# MegaShieldTrioV2.net
KiCad netlist of a schematic drawn in EAGLE
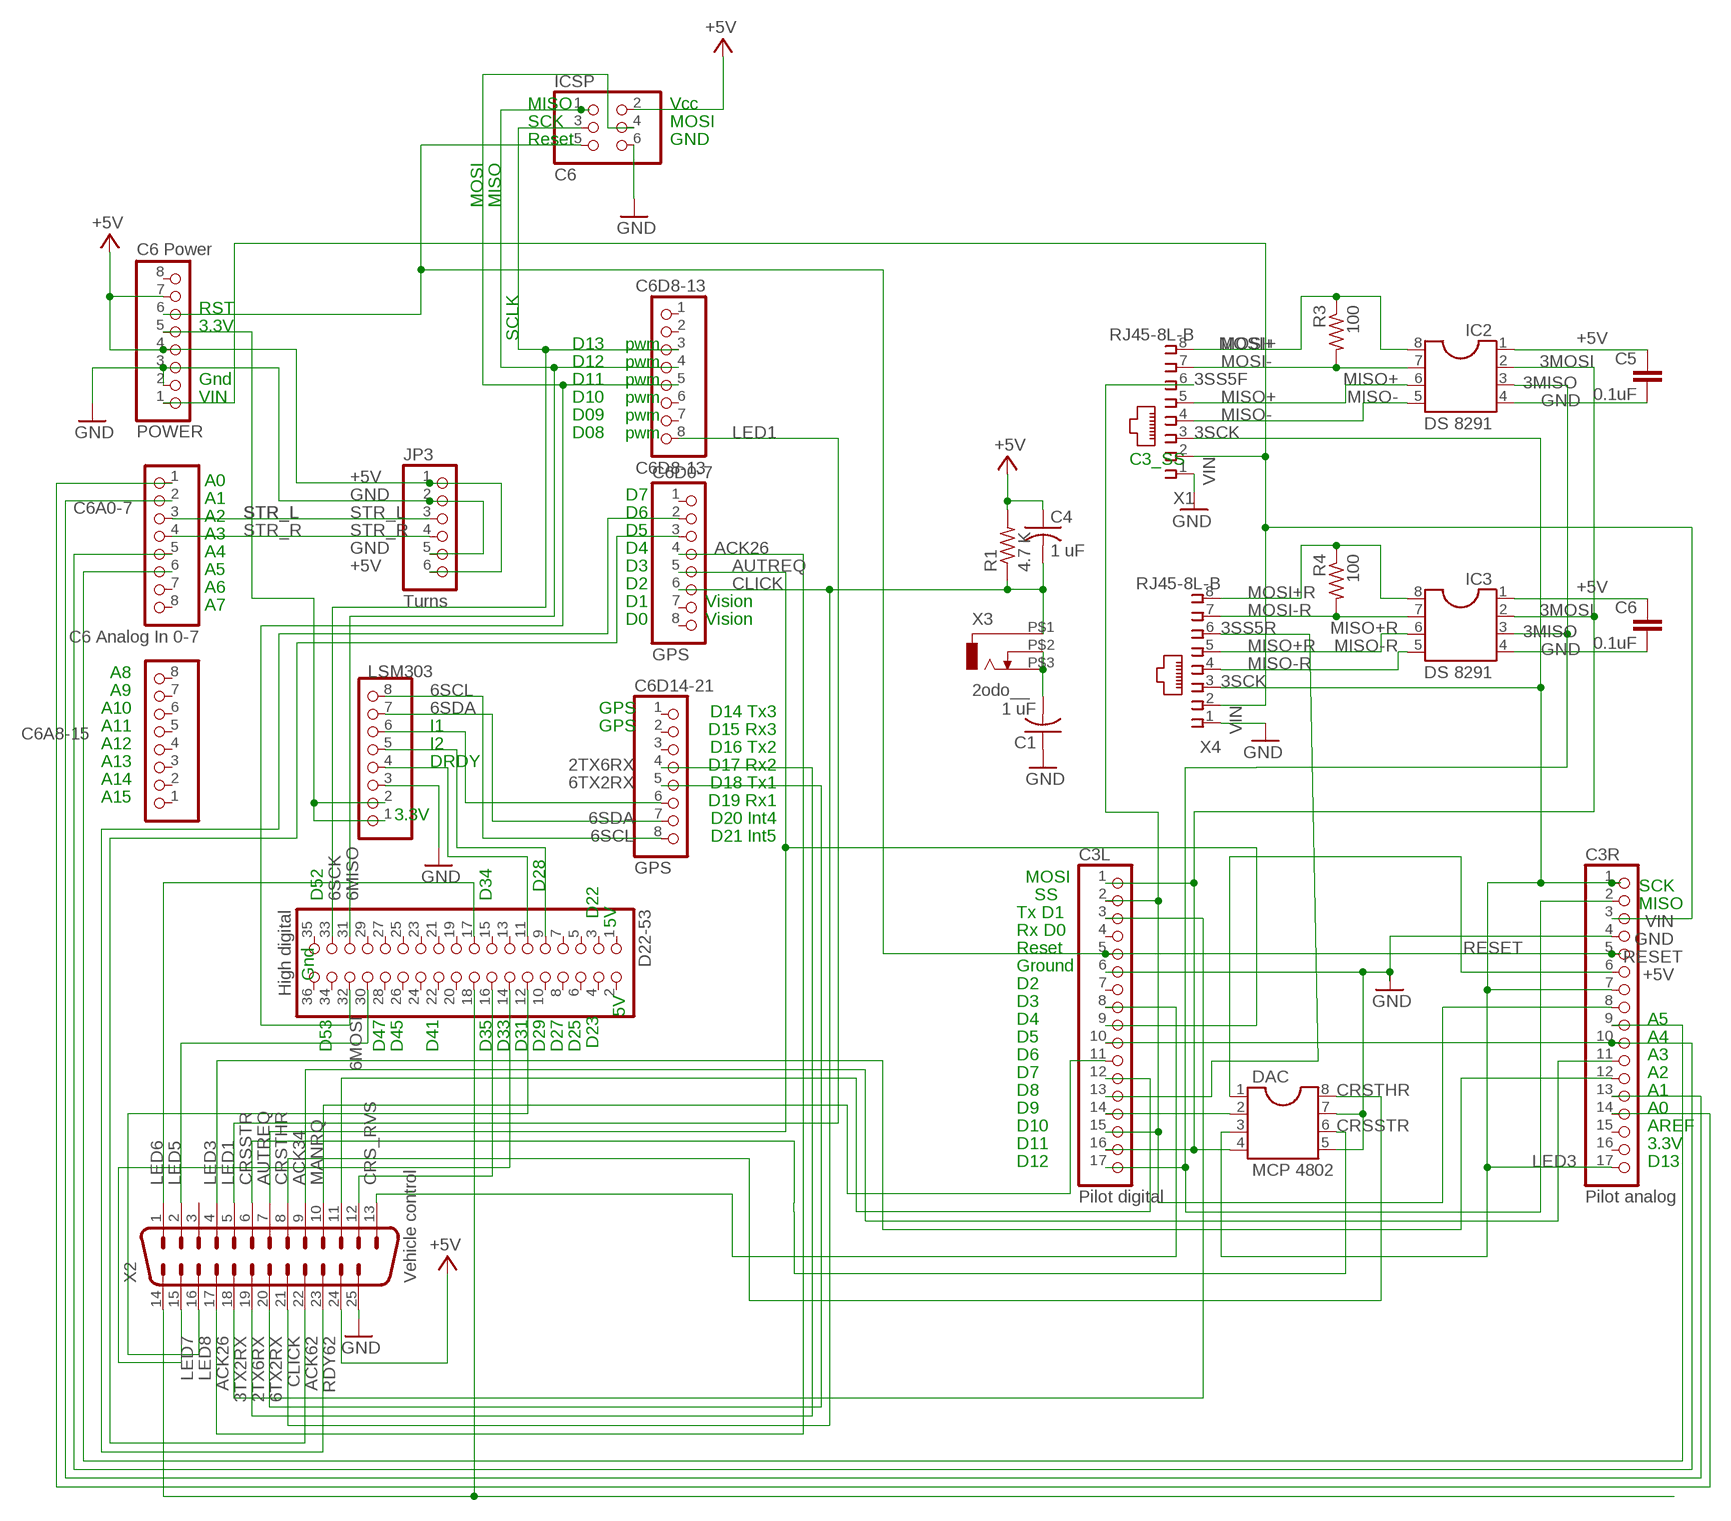
[diagram p0: schematic, sheet 1]

(export (version "E")
  (design (tool "Eeschema 10.0.6"))
  (components
    (comp (ref "C1")
      (value "1 uF")
      (footprint "eagle-import:C025-030X050")
      (libsource (lib "eagle-import") (part "C-US025-030X050"))
    )
    (comp (ref "C3L")
      (value "Pilot digital")
      (footprint "eagle-import:1X17")
      (libsource (lib "eagle-import") (part "PINHD-1X17"))
    )
    (comp (ref "C3R")
      (value "Pilot analog")
      (footprint "eagle-import:1X17")
      (libsource (lib "eagle-import") (part "PINHD-1X17"))
    )
    (comp (ref "C4")
      (value "1 uF")
      (footprint "eagle-import:C025-030X050")
      (libsource (lib "eagle-import") (part "C-US025-030X050"))
    )
    (comp (ref "C5")
      (value "0.1uF")
      (footprint "eagle-import:C2.5-2")
      (libsource (lib "eagle-import") (part "C2.5/2"))
    )
    (comp (ref "C6")
      (value "0.1uF")
      (footprint "eagle-import:C2.5-2")
      (libsource (lib "eagle-import") (part "C2.5/2"))
    )
    (comp (ref "C6A0-7")
      (value "C6 Analog In 0-7")
      (footprint "eagle-import:1X08")
      (libsource (lib "eagle-import") (part "PINHD-1X8"))
    )
    (comp (ref "C6A8-15")
      (value "PINHD-1X8")
      (footprint "eagle-import:1X08")
      (libsource (lib "eagle-import") (part "PINHD-1X8"))
    )
    (comp (ref "C6D0-7")
      (value "GPS")
      (footprint "eagle-import:1X08")
      (libsource (lib "eagle-import") (part "PINHD-1X8"))
    )
    (comp (ref "C6D8-13")
      (value "C6D8-13")
      (footprint "eagle-import:1X08")
      (libsource (lib "eagle-import") (part "PINHD-1X8"))
    )
    (comp (ref "C6D14-21")
      (value "GPS")
      (footprint "eagle-import:1X08")
      (libsource (lib "eagle-import") (part "PINHD-1X8"))
    )
    (comp (ref "D22-53")
      (value "High digital")
      (footprint "eagle-import:2X18")
      (libsource (lib "eagle-import") (part "PINHD-2X18"))
    )
    (comp (ref "DAC")
      (value "MCP 4802")
      (footprint "eagle-import:DIL08")
      (libsource (lib "eagle-import") (part "DIL8"))
    )
    (comp (ref "IC2")
      (value "DS 8291")
      (footprint "eagle-import:DIL08")
      (libsource (lib "eagle-import") (part "DIL8"))
    )
    (comp (ref "IC3")
      (value "DS 8291")
      (footprint "eagle-import:DIL08")
      (libsource (lib "eagle-import") (part "DIL8"))
    )
    (comp (ref "ICSP")
      (value "C6")
      (footprint "eagle-import:2X03")
      (libsource (lib "eagle-import") (part "PINHD-2X3"))
    )
    (comp (ref "JP3")
      (value "Turns")
      (footprint "eagle-import:1X06")
      (libsource (lib "eagle-import") (part "PINHD-1X6"))
    )
    (comp (ref "LSM303")
      (value "PINHD-1X8")
      (footprint "eagle-import:1X08")
      (libsource (lib "eagle-import") (part "PINHD-1X8"))
    )
    (comp (ref "POWER")
      (value "C6 Power")
      (footprint "eagle-import:1X08")
      (libsource (lib "eagle-import") (part "PINHD-1X8"))
    )
    (comp (ref "R1")
      (value "4.7 K")
      (footprint "eagle-import:0207_10")
      (libsource (lib "eagle-import") (part "R-US_0207/10"))
    )
    (comp (ref "R3")
      (value "100")
      (footprint "eagle-import:0204_5")
      (libsource (lib "eagle-import") (part "resistor_R-US_0204/5"))
    )
    (comp (ref "R4")
      (value "100")
      (footprint "eagle-import:0204_5")
      (libsource (lib "eagle-import") (part "resistor_R-US_0204/5"))
    )
    (comp (ref "X1")
      (value "RJ45-8L-B")
      (footprint "eagle-import:RJ45-NO-SHIELD")
      (fields (field (name "MF") "TYCO ELECTRONICS"))
      (libsource (lib "eagle-import") (part "RJ45-8L-B"))
    )
    (comp (ref "X2")
      (value "Vehicle control")
      (footprint "eagle-import:M25H")
      (libsource (lib "eagle-import") (part "M25H"))
    )
    (comp (ref "X3")
      (value "2odo__")
      (footprint "eagle-import:ODO_JACK")
      (libsource (lib "eagle-import") (part "ODO_JACK"))
    )
    (comp (ref "X4")
      (value "RJ45-8L-B")
      (footprint "eagle-import:RJ45-NO-SHIELD")
      (fields (field (name "MF") "TYCO ELECTRONICS"))
      (libsource (lib "eagle-import") (part "RJ45-8L-B"))
    )
  )
  (nets
    (net (code "1") (name "+5V") (class "Default")
      (node (ref "C4") (pin "1") (pinfunction "1_1") (pintype "passive"))
      (node (ref "C5") (pin "1") (pinfunction "1_1") (pintype "passive"))
      (node (ref "C6") (pin "1") (pinfunction "1_1") (pintype "passive"))
      (node (ref "IC2") (pin "1") (pinfunction "1_1") (pintype "passive"))
      (node (ref "IC3") (pin "1") (pinfunction "1_1") (pintype "passive"))
      (node (ref "ICSP") (pin "2") (pinfunction "2_2") (pintype "passive"))
      (node (ref "JP3") (pin "1") (pinfunction "1_1") (pintype "passive"))
      (node (ref "JP3") (pin "6") (pinfunction "6_6") (pintype "passive"))
      (node (ref "POWER") (pin "4") (pinfunction "4_4") (pintype "passive"))
      (node (ref "POWER") (pin "7") (pinfunction "7_7") (pintype "passive"))
      (node (ref "R1") (pin "2") (pinfunction "2_2") (pintype "passive"))
      (node (ref "X2") (pin "24") (pinfunction "24_24") (pintype "passive"))
    )
    (net (code "2") (name "/2TX6RX") (class "Default")
      (node (ref "C6D14-21") (pin "4") (pinfunction "4_4") (pintype "passive"))
      (node (ref "X2") (pin "19") (pinfunction "19_19") (pintype "passive"))
    )
    (net (code "3") (name "/3MISO") (class "Default")
      (node (ref "C3L") (pin "17") (pinfunction "17_17") (pintype "passive"))
      (node (ref "C3R") (pin "2") (pinfunction "2_2") (pintype "passive"))
      (node (ref "IC2") (pin "3") (pinfunction "3_3") (pintype "passive"))
      (node (ref "IC3") (pin "3") (pinfunction "3_3") (pintype "passive"))
    )
    (net (code "4") (name "/3MOSI") (class "Default")
      (node (ref "C3L") (pin "1") (pinfunction "1_1") (pintype "passive"))
      (node (ref "C3L") (pin "16") (pinfunction "16_16") (pintype "passive"))
      (node (ref "DAC") (pin "4") (pinfunction "4_4") (pintype "passive"))
      (node (ref "IC2") (pin "2") (pinfunction "2_2") (pintype "passive"))
      (node (ref "IC3") (pin "2") (pinfunction "2_2") (pintype "passive"))
    )
    (net (code "5") (name "/3SCK") (class "Default")
      (node (ref "C3R") (pin "1") (pinfunction "1_1") (pintype "passive"))
      (node (ref "C3R") (pin "17") (pinfunction "17_17") (pintype "passive"))
      (node (ref "C3R") (pin "7") (pinfunction "7_7") (pintype "passive"))
      (node (ref "DAC") (pin "3") (pinfunction "3_3") (pintype "passive"))
      (node (ref "X1") (pin "3") (pinfunction "3_3") (pintype "passive"))
      (node (ref "X4") (pin "3") (pinfunction "3_3") (pintype "passive"))
    )
    (net (code "6") (name "/3SS5F") (class "Default")
      (node (ref "C3L") (pin "15") (pinfunction "15_15") (pintype "passive"))
      (node (ref "C3L") (pin "2") (pinfunction "2_2") (pintype "passive"))
      (node (ref "C3R") (pin "8") (pinfunction "8_8") (pintype "passive"))
      (node (ref "X1") (pin "6") (pinfunction "6_6") (pintype "passive"))
    )
    (net (code "7") (name "/3SS5R") (class "Default")
      (node (ref "C3L") (pin "13") (pinfunction "13_13") (pintype "passive"))
      (node (ref "X4") (pin "6") (pinfunction "6_6") (pintype "passive"))
    )
    (net (code "8") (name "/3TX2RX") (class "Default")
      (node (ref "C3L") (pin "3") (pinfunction "3_3") (pintype "passive"))
      (node (ref "X2") (pin "18") (pinfunction "18_18") (pintype "passive"))
    )
    (net (code "9") (name "/6MISO") (class "Default")
      (node (ref "C6D8-13") (pin "4") (pinfunction "4_4") (pintype "passive"))
      (node (ref "D22-53") (pin "31") (pinfunction "31_31") (pintype "passive"))
      (node (ref "ICSP") (pin "1") (pinfunction "1_1") (pintype "passive"))
    )
    (net (code "10") (name "/6MOSI") (class "Default")
      (node (ref "C6D8-13") (pin "5") (pinfunction "5_5") (pintype "passive"))
      (node (ref "D22-53") (pin "32") (pinfunction "32_32") (pintype "passive"))
      (node (ref "ICSP") (pin "4") (pinfunction "4_4") (pintype "passive"))
    )
    (net (code "11") (name "/6SCK") (class "Default")
      (node (ref "C6D8-13") (pin "3") (pinfunction "3_3") (pintype "passive"))
      (node (ref "D22-53") (pin "33") (pinfunction "33_33") (pintype "passive"))
      (node (ref "ICSP") (pin "3") (pinfunction "3_3") (pintype "passive"))
    )
    (net (code "12") (name "/6SCL") (class "Default")
      (node (ref "C6D14-21") (pin "8") (pinfunction "8_8") (pintype "passive"))
      (node (ref "LSM303") (pin "8") (pinfunction "8_8") (pintype "passive"))
    )
    (net (code "13") (name "/6SDA") (class "Default")
      (node (ref "C6D14-21") (pin "7") (pinfunction "7_7") (pintype "passive"))
      (node (ref "LSM303") (pin "7") (pinfunction "7_7") (pintype "passive"))
    )
    (net (code "14") (name "/6TX2RX") (class "Default")
      (node (ref "C6D14-21") (pin "5") (pinfunction "5_5") (pintype "passive"))
      (node (ref "X2") (pin "20") (pinfunction "20_20") (pintype "passive"))
    )
    (net (code "15") (name "/ACK26") (class "Default")
      (node (ref "C6D0-7") (pin "4") (pinfunction "4_4") (pintype "passive"))
      (node (ref "X2") (pin "17") (pinfunction "17_17") (pintype "passive"))
    )
    (net (code "16") (name "/ACK34") (class "Default")
      (node (ref "C3R") (pin "11") (pinfunction "11_11") (pintype "passive"))
      (node (ref "X2") (pin "9") (pinfunction "9_9") (pintype "passive"))
    )
    (net (code "17") (name "/ACK62") (class "Default")
      (node (ref "C6D0-7") (pin "3") (pinfunction "3_3") (pintype "passive"))
      (node (ref "X2") (pin "22") (pinfunction "22_22") (pintype "passive"))
    )
    (net (code "18") (name "/AUTREQ") (class "Default")
      (node (ref "C3L") (pin "9") (pinfunction "9_9") (pintype "passive"))
      (node (ref "C6D0-7") (pin "5") (pinfunction "5_5") (pintype "passive"))
      (node (ref "X2") (pin "7") (pinfunction "7_7") (pintype "passive"))
    )
    (net (code "19") (name "/CLICK") (class "Default")
      (node (ref "C4") (pin "2") (pinfunction "2_2") (pintype "passive"))
      (node (ref "C6D0-7") (pin "6") (pinfunction "6_6") (pintype "passive"))
      (node (ref "R1") (pin "1") (pinfunction "1_1") (pintype "passive"))
      (node (ref "X2") (pin "21") (pinfunction "21_21") (pintype "passive"))
      (node (ref "X3") (pin "P$1") (pinfunction "1_P$1") (pintype "passive"))
    )
    (net (code "20") (name "/CRSSTR") (class "Default")
      (node (ref "DAC") (pin "6") (pinfunction "6_6") (pintype "passive"))
      (node (ref "X2") (pin "6") (pinfunction "6_6") (pintype "passive"))
    )
    (net (code "21") (name "/CRSTHR") (class "Default")
      (node (ref "DAC") (pin "8") (pinfunction "8_8") (pintype "passive"))
      (node (ref "X2") (pin "8") (pinfunction "8_8") (pintype "passive"))
    )
    (net (code "22") (name "/CRS_RVS") (class "Default")
      (node (ref "C3L") (pin "8") (pinfunction "8_8") (pintype "passive"))
      (node (ref "X2") (pin "13") (pinfunction "13_13") (pintype "passive"))
    )
    (net (code "23") (name "/LED1") (class "Default")
      (node (ref "C6D8-13") (pin "8") (pinfunction "8_8") (pintype "passive"))
      (node (ref "X2") (pin "5") (pinfunction "5_5") (pintype "passive"))
    )
    (net (code "24") (name "/LED3") (class "Default")
      (node (ref "C3R") (pin "12") (pinfunction "12_12") (pintype "passive"))
      (node (ref "X2") (pin "4") (pinfunction "4_4") (pintype "passive"))
    )
    (net (code "25") (name "/LED5") (class "Default")
      (node (ref "D22-53") (pin "30") (pinfunction "30_30") (pintype "passive"))
      (node (ref "X2") (pin "2") (pinfunction "2_2") (pintype "passive"))
    )
    (net (code "26") (name "/LED6") (class "Default")
      (node (ref "D22-53") (pin "17") (pinfunction "17_17") (pintype "passive"))
      (node (ref "X2") (pin "1") (pinfunction "1_1") (pintype "passive"))
    )
    (net (code "27") (name "/LED7") (class "Default")
      (node (ref "D22-53") (pin "14") (pinfunction "14_14") (pintype "passive"))
      (node (ref "X2") (pin "15") (pinfunction "15_15") (pintype "passive"))
    )
    (net (code "28") (name "/LED8") (class "Default")
      (node (ref "D22-53") (pin "12") (pinfunction "12_12") (pintype "passive"))
      (node (ref "X2") (pin "16") (pinfunction "16_16") (pintype "passive"))
    )
    (net (code "29") (name "/MANRQ") (class "Default")
      (node (ref "C3L") (pin "11") (pinfunction "11_11") (pintype "passive"))
      (node (ref "X2") (pin "10") (pinfunction "10_10") (pintype "passive"))
    )
    (net (code "30") (name "/MISO+") (class "Default")
      (node (ref "IC2") (pin "6") (pinfunction "6_6") (pintype "passive"))
      (node (ref "X1") (pin "5") (pinfunction "5_5") (pintype "passive"))
    )
    (net (code "31") (name "/MISO+R") (class "Default")
      (node (ref "IC3") (pin "6") (pinfunction "6_6") (pintype "passive"))
      (node (ref "X4") (pin "5") (pinfunction "5_5") (pintype "passive"))
    )
    (net (code "32") (name "/MISO-") (class "Default")
      (node (ref "IC2") (pin "5") (pinfunction "5_5") (pintype "passive"))
      (node (ref "X1") (pin "4") (pinfunction "4_4") (pintype "passive"))
    )
    (net (code "33") (name "/MISO-R") (class "Default")
      (node (ref "IC3") (pin "5") (pinfunction "5_5") (pintype "passive"))
      (node (ref "X4") (pin "4") (pinfunction "4_4") (pintype "passive"))
    )
    (net (code "34") (name "/MOSI+") (class "Default")
      (node (ref "IC2") (pin "8") (pinfunction "8_8") (pintype "passive"))
      (node (ref "R3") (pin "1") (pinfunction "1_1") (pintype "passive"))
      (node (ref "X1") (pin "8") (pinfunction "8_8") (pintype "passive"))
    )
    (net (code "35") (name "/MOSI+R") (class "Default")
      (node (ref "IC3") (pin "8") (pinfunction "8_8") (pintype "passive"))
      (node (ref "R4") (pin "1") (pinfunction "1_1") (pintype "passive"))
      (node (ref "X4") (pin "8") (pinfunction "8_8") (pintype "passive"))
    )
    (net (code "36") (name "/MOSI-") (class "Default")
      (node (ref "IC2") (pin "7") (pinfunction "7_7") (pintype "passive"))
      (node (ref "R3") (pin "2") (pinfunction "2_2") (pintype "passive"))
      (node (ref "X1") (pin "7") (pinfunction "7_7") (pintype "passive"))
    )
    (net (code "37") (name "/MOSI-R") (class "Default")
      (node (ref "IC3") (pin "7") (pinfunction "7_7") (pintype "passive"))
      (node (ref "R4") (pin "2") (pinfunction "2_2") (pintype "passive"))
      (node (ref "X4") (pin "7") (pinfunction "7_7") (pintype "passive"))
    )
    (net (code "38") (name "/RDY62") (class "Default")
      (node (ref "C6D0-7") (pin "2") (pinfunction "2_2") (pintype "passive"))
      (node (ref "X2") (pin "23") (pinfunction "23_23") (pintype "passive"))
    )
    (net (code "39") (name "/RESET") (class "Default")
      (node (ref "C3L") (pin "5") (pinfunction "5_5") (pintype "passive"))
      (node (ref "C3R") (pin "5") (pinfunction "5_5") (pintype "passive"))
      (node (ref "ICSP") (pin "5") (pinfunction "5_5") (pintype "passive"))
      (node (ref "POWER") (pin "6") (pinfunction "6_6") (pintype "passive"))
    )
    (net (code "40") (name "/STR_L") (class "Default")
      (node (ref "C6A0-7") (pin "3") (pinfunction "3_3") (pintype "passive"))
      (node (ref "JP3") (pin "3") (pinfunction "3_3") (pintype "passive"))
    )
    (net (code "41") (name "/STR_R") (class "Default")
      (node (ref "C6A0-7") (pin "4") (pinfunction "4_4") (pintype "passive"))
      (node (ref "JP3") (pin "4") (pinfunction "4_4") (pintype "passive"))
    )
    (net (code "42") (name "/VIN") (class "Default")
      (node (ref "C3R") (pin "3") (pinfunction "3_3") (pintype "passive"))
      (node (ref "POWER") (pin "1") (pinfunction "1_1") (pintype "passive"))
      (node (ref "X1") (pin "2") (pinfunction "2_2") (pintype "passive"))
      (node (ref "X4") (pin "2") (pinfunction "2_2") (pintype "passive"))
    )
    (net (code "43") (name "GND") (class "Default")
      (node (ref "C1") (pin "1") (pinfunction "1_1") (pintype "passive"))
      (node (ref "C3L") (pin "6") (pinfunction "6_6") (pintype "passive"))
      (node (ref "C3R") (pin "4") (pinfunction "4_4") (pintype "passive"))
      (node (ref "C5") (pin "2") (pinfunction "2_2") (pintype "passive"))
      (node (ref "C6") (pin "2") (pinfunction "2_2") (pintype "passive"))
      (node (ref "DAC") (pin "5") (pinfunction "5_5") (pintype "passive"))
      (node (ref "DAC") (pin "7") (pinfunction "7_7") (pintype "passive"))
      (node (ref "IC2") (pin "4") (pinfunction "4_4") (pintype "passive"))
      (node (ref "IC3") (pin "4") (pinfunction "4_4") (pintype "passive"))
      (node (ref "ICSP") (pin "6") (pinfunction "6_6") (pintype "passive"))
      (node (ref "JP3") (pin "2") (pinfunction "2_2") (pintype "passive"))
      (node (ref "JP3") (pin "5") (pinfunction "5_5") (pintype "passive"))
      (node (ref "LSM303") (pin "3") (pinfunction "3_3") (pintype "passive"))
      (node (ref "POWER") (pin "2") (pinfunction "2_2") (pintype "passive"))
      (node (ref "POWER") (pin "3") (pinfunction "3_3") (pintype "passive"))
      (node (ref "X1") (pin "1") (pinfunction "1_1") (pintype "passive"))
      (node (ref "X2") (pin "25") (pinfunction "25_25") (pintype "passive"))
      (node (ref "X4") (pin "1") (pinfunction "1_1") (pintype "passive"))
    )
    (net (code "44") (name "Net-(C3L-Pad10)") (class "Default")
      (node (ref "C3L") (pin "10") (pinfunction "10_10") (pintype "passive"))
      (node (ref "C3R") (pin "10") (pinfunction "10_10") (pintype "passive"))
      (node (ref "C6A0-7") (pin "5") (pinfunction "5_5") (pintype "passive"))
    )
    (net (code "45") (name "Net-(C3L-Pad12)") (class "Default")
      (node (ref "C3L") (pin "12") (pinfunction "12_12") (pintype "passive"))
      (node (ref "X2") (pin "11") (pinfunction "11_11") (pintype "passive"))
    )
    (net (code "46") (name "Net-(C3L-Pad14)") (class "Default")
      (node (ref "C3L") (pin "14") (pinfunction "14_14") (pintype "passive"))
      (node (ref "DAC") (pin "2") (pinfunction "2_2") (pintype "passive"))
    )
    (net (code "47") (name "Net-(C3R-Pad6)") (class "Default")
      (node (ref "C3R") (pin "6") (pinfunction "6_6") (pintype "passive"))
      (node (ref "DAC") (pin "1") (pinfunction "1_1") (pintype "passive"))
    )
    (net (code "48") (name "Net-(C3R-Pad9)") (class "Default")
      (node (ref "C3R") (pin "9") (pinfunction "9_9") (pintype "passive"))
      (node (ref "C6A0-7") (pin "6") (pinfunction "6_6") (pintype "passive"))
    )
    (net (code "49") (name "Net-(C3R-Pad13)") (class "Default")
      (node (ref "C3R") (pin "13") (pinfunction "13_13") (pintype "passive"))
      (node (ref "C6A0-7") (pin "2") (pinfunction "2_2") (pintype "passive"))
    )
    (net (code "50") (name "Net-(C3R-Pad14)") (class "Default")
      (node (ref "C3R") (pin "14") (pinfunction "14_14") (pintype "passive"))
      (node (ref "C6A0-7") (pin "1") (pinfunction "1_1") (pintype "passive"))
    )
    (net (code "51") (name "Net-(C6D14-21-Pad6)") (class "Default")
      (node (ref "C6D14-21") (pin "6") (pinfunction "6_6") (pintype "passive"))
      (node (ref "LSM303") (pin "6") (pinfunction "6_6") (pintype "passive"))
    )
    (net (code "52") (name "Net-(D22-53-Pad9)") (class "Default")
      (node (ref "D22-53") (pin "9") (pinfunction "9_9") (pintype "passive"))
      (node (ref "LSM303") (pin "5") (pinfunction "5_5") (pintype "passive"))
    )
    (net (code "53") (name "Net-(D22-53-Pad11)") (class "Default")
      (node (ref "D22-53") (pin "11") (pinfunction "11_11") (pintype "passive"))
      (node (ref "LSM303") (pin "4") (pinfunction "4_4") (pintype "passive"))
    )
    (net (code "54") (name "Net-(D22-53-Pad16)") (class "Default")
      (node (ref "D22-53") (pin "16") (pinfunction "16_16") (pintype "passive"))
      (node (ref "X2") (pin "12") (pinfunction "12_12") (pintype "passive"))
    )
    (net (code "55") (name "Net-(D22-53-Pad18)") (class "Default")
      (node (ref "D22-53") (pin "18") (pinfunction "18_18") (pintype "passive"))
      (node (ref "X2") (pin "14") (pinfunction "14_14") (pintype "passive"))
    )
    (net (code "56") (name "Net-(LSM303-Pad1)") (class "Default")
      (node (ref "LSM303") (pin "1") (pinfunction "1_1") (pintype "passive"))
      (node (ref "LSM303") (pin "2") (pinfunction "2_2") (pintype "passive"))
      (node (ref "POWER") (pin "5") (pinfunction "5_5") (pintype "passive"))
    )
    (net (code "57") (name "Net-(X3-2)") (class "Default")
      (node (ref "C1") (pin "2") (pinfunction "2_2") (pintype "passive"))
      (node (ref "X3") (pin "P$2") (pinfunction "2_P$2") (pintype "passive"))
      (node (ref "X3") (pin "P$3") (pinfunction "3_P$3") (pintype "passive"))
    )
    (net (code "58") (name "unconnected-(C3L-Pad4)") (class "Default")
      (node (ref "C3L") (pin "4") (pinfunction "4_4") (pintype "passive"))
    )
    (net (code "59") (name "unconnected-(C3L-Pad7)") (class "Default")
      (node (ref "C3L") (pin "7") (pinfunction "7_7") (pintype "passive"))
    )
    (net (code "60") (name "unconnected-(C3R-Pad15)") (class "Default")
      (node (ref "C3R") (pin "15") (pinfunction "15_15") (pintype "passive"))
    )
    (net (code "61") (name "unconnected-(C3R-Pad16)") (class "Default")
      (node (ref "C3R") (pin "16") (pinfunction "16_16") (pintype "passive"))
    )
    (net (code "62") (name "unconnected-(C6A0-7-Pad7)") (class "Default")
      (node (ref "C6A0-7") (pin "7") (pinfunction "7_7") (pintype "passive"))
    )
    (net (code "63") (name "unconnected-(C6A0-7-Pad8)") (class "Default")
      (node (ref "C6A0-7") (pin "8") (pinfunction "8_8") (pintype "passive"))
    )
    (net (code "64") (name "unconnected-(C6A8-15-Pad1)") (class "Default")
      (node (ref "C6A8-15") (pin "1") (pinfunction "1_1") (pintype "passive"))
    )
    (net (code "65") (name "unconnected-(C6A8-15-Pad2)") (class "Default")
      (node (ref "C6A8-15") (pin "2") (pinfunction "2_2") (pintype "passive"))
    )
    (net (code "66") (name "unconnected-(C6A8-15-Pad3)") (class "Default")
      (node (ref "C6A8-15") (pin "3") (pinfunction "3_3") (pintype "passive"))
    )
    (net (code "67") (name "unconnected-(C6A8-15-Pad4)") (class "Default")
      (node (ref "C6A8-15") (pin "4") (pinfunction "4_4") (pintype "passive"))
    )
    (net (code "68") (name "unconnected-(C6A8-15-Pad5)") (class "Default")
      (node (ref "C6A8-15") (pin "5") (pinfunction "5_5") (pintype "passive"))
    )
    (net (code "69") (name "unconnected-(C6A8-15-Pad6)") (class "Default")
      (node (ref "C6A8-15") (pin "6") (pinfunction "6_6") (pintype "passive"))
    )
    (net (code "70") (name "unconnected-(C6A8-15-Pad7)") (class "Default")
      (node (ref "C6A8-15") (pin "7") (pinfunction "7_7") (pintype "passive"))
    )
    (net (code "71") (name "unconnected-(C6A8-15-Pad8)") (class "Default")
      (node (ref "C6A8-15") (pin "8") (pinfunction "8_8") (pintype "passive"))
    )
    (net (code "72") (name "unconnected-(C6D0-7-Pad1)") (class "Default")
      (node (ref "C6D0-7") (pin "1") (pinfunction "1_1") (pintype "passive"))
    )
    (net (code "73") (name "unconnected-(C6D0-7-Pad7)") (class "Default")
      (node (ref "C6D0-7") (pin "7") (pinfunction "7_7") (pintype "passive"))
    )
    (net (code "74") (name "unconnected-(C6D0-7-Pad8)") (class "Default")
      (node (ref "C6D0-7") (pin "8") (pinfunction "8_8") (pintype "passive"))
    )
    (net (code "75") (name "unconnected-(C6D8-13-Pad1)") (class "Default")
      (node (ref "C6D8-13") (pin "1") (pinfunction "1_1") (pintype "passive"))
    )
    (net (code "76") (name "unconnected-(C6D8-13-Pad2)") (class "Default")
      (node (ref "C6D8-13") (pin "2") (pinfunction "2_2") (pintype "passive"))
    )
    (net (code "77") (name "unconnected-(C6D8-13-Pad6)") (class "Default")
      (node (ref "C6D8-13") (pin "6") (pinfunction "6_6") (pintype "passive"))
    )
    (net (code "78") (name "unconnected-(C6D8-13-Pad7)") (class "Default")
      (node (ref "C6D8-13") (pin "7") (pinfunction "7_7") (pintype "passive"))
    )
    (net (code "79") (name "unconnected-(C6D14-21-Pad1)") (class "Default")
      (node (ref "C6D14-21") (pin "1") (pinfunction "1_1") (pintype "passive"))
    )
    (net (code "80") (name "unconnected-(C6D14-21-Pad2)") (class "Default")
      (node (ref "C6D14-21") (pin "2") (pinfunction "2_2") (pintype "passive"))
    )
    (net (code "81") (name "unconnected-(C6D14-21-Pad3)") (class "Default")
      (node (ref "C6D14-21") (pin "3") (pinfunction "3_3") (pintype "passive"))
    )
    (net (code "82") (name "unconnected-(D22-53-Pad1)") (class "Default")
      (node (ref "D22-53") (pin "1") (pinfunction "1_1") (pintype "passive"))
    )
    (net (code "83") (name "unconnected-(D22-53-Pad2)") (class "Default")
      (node (ref "D22-53") (pin "2") (pinfunction "2_2") (pintype "passive"))
    )
    (net (code "84") (name "unconnected-(D22-53-Pad3)") (class "Default")
      (node (ref "D22-53") (pin "3") (pinfunction "3_3") (pintype "passive"))
    )
    (net (code "85") (name "unconnected-(D22-53-Pad4)") (class "Default")
      (node (ref "D22-53") (pin "4") (pinfunction "4_4") (pintype "passive"))
    )
    (net (code "86") (name "unconnected-(D22-53-Pad5)") (class "Default")
      (node (ref "D22-53") (pin "5") (pinfunction "5_5") (pintype "passive"))
    )
    (net (code "87") (name "unconnected-(D22-53-Pad6)") (class "Default")
      (node (ref "D22-53") (pin "6") (pinfunction "6_6") (pintype "passive"))
    )
    (net (code "88") (name "unconnected-(D22-53-Pad7)") (class "Default")
      (node (ref "D22-53") (pin "7") (pinfunction "7_7") (pintype "passive"))
    )
    (net (code "89") (name "unconnected-(D22-53-Pad8)") (class "Default")
      (node (ref "D22-53") (pin "8") (pinfunction "8_8") (pintype "passive"))
    )
    (net (code "90") (name "unconnected-(D22-53-Pad10)") (class "Default")
      (node (ref "D22-53") (pin "10") (pinfunction "10_10") (pintype "passive"))
    )
    (net (code "91") (name "unconnected-(D22-53-Pad13)") (class "Default")
      (node (ref "D22-53") (pin "13") (pinfunction "13_13") (pintype "passive"))
    )
    (net (code "92") (name "unconnected-(D22-53-Pad15)") (class "Default")
      (node (ref "D22-53") (pin "15") (pinfunction "15_15") (pintype "passive"))
    )
    (net (code "93") (name "unconnected-(D22-53-Pad19)") (class "Default")
      (node (ref "D22-53") (pin "19") (pinfunction "19_19") (pintype "passive"))
    )
    (net (code "94") (name "unconnected-(D22-53-Pad20)") (class "Default")
      (node (ref "D22-53") (pin "20") (pinfunction "20_20") (pintype "passive"))
    )
    (net (code "95") (name "unconnected-(D22-53-Pad21)") (class "Default")
      (node (ref "D22-53") (pin "21") (pinfunction "21_21") (pintype "passive"))
    )
    (net (code "96") (name "unconnected-(D22-53-Pad22)") (class "Default")
      (node (ref "D22-53") (pin "22") (pinfunction "22_22") (pintype "passive"))
    )
    (net (code "97") (name "unconnected-(D22-53-Pad23)") (class "Default")
      (node (ref "D22-53") (pin "23") (pinfunction "23_23") (pintype "passive"))
    )
    (net (code "98") (name "unconnected-(D22-53-Pad24)") (class "Default")
      (node (ref "D22-53") (pin "24") (pinfunction "24_24") (pintype "passive"))
    )
    (net (code "99") (name "unconnected-(D22-53-Pad25)") (class "Default")
      (node (ref "D22-53") (pin "25") (pinfunction "25_25") (pintype "passive"))
    )
    (net (code "100") (name "unconnected-(D22-53-Pad26)") (class "Default")
      (node (ref "D22-53") (pin "26") (pinfunction "26_26") (pintype "passive"))
    )
    (net (code "101") (name "unconnected-(D22-53-Pad27)") (class "Default")
      (node (ref "D22-53") (pin "27") (pinfunction "27_27") (pintype "passive"))
    )
    (net (code "102") (name "unconnected-(D22-53-Pad28)") (class "Default")
      (node (ref "D22-53") (pin "28") (pinfunction "28_28") (pintype "passive"))
    )
    (net (code "103") (name "unconnected-(D22-53-Pad29)") (class "Default")
      (node (ref "D22-53") (pin "29") (pinfunction "29_29") (pintype "passive"))
    )
    (net (code "104") (name "unconnected-(D22-53-Pad34)") (class "Default")
      (node (ref "D22-53") (pin "34") (pinfunction "34_34") (pintype "passive"))
    )
    (net (code "105") (name "unconnected-(D22-53-Pad35)") (class "Default")
      (node (ref "D22-53") (pin "35") (pinfunction "35_35") (pintype "passive"))
    )
    (net (code "106") (name "unconnected-(D22-53-Pad36)") (class "Default")
      (node (ref "D22-53") (pin "36") (pinfunction "36_36") (pintype "passive"))
    )
    (net (code "107") (name "unconnected-(POWER-Pad8)") (class "Default")
      (node (ref "POWER") (pin "8") (pinfunction "8_8") (pintype "passive"))
    )
    (net (code "108") (name "unconnected-(X2-Pad3)") (class "Default")
      (node (ref "X2") (pin "3") (pinfunction "3_3") (pintype "passive"))
    )
  )
)
